# fretscanner-INPUTS.net
KiCad netlist of a schematic drawn in EAGLE
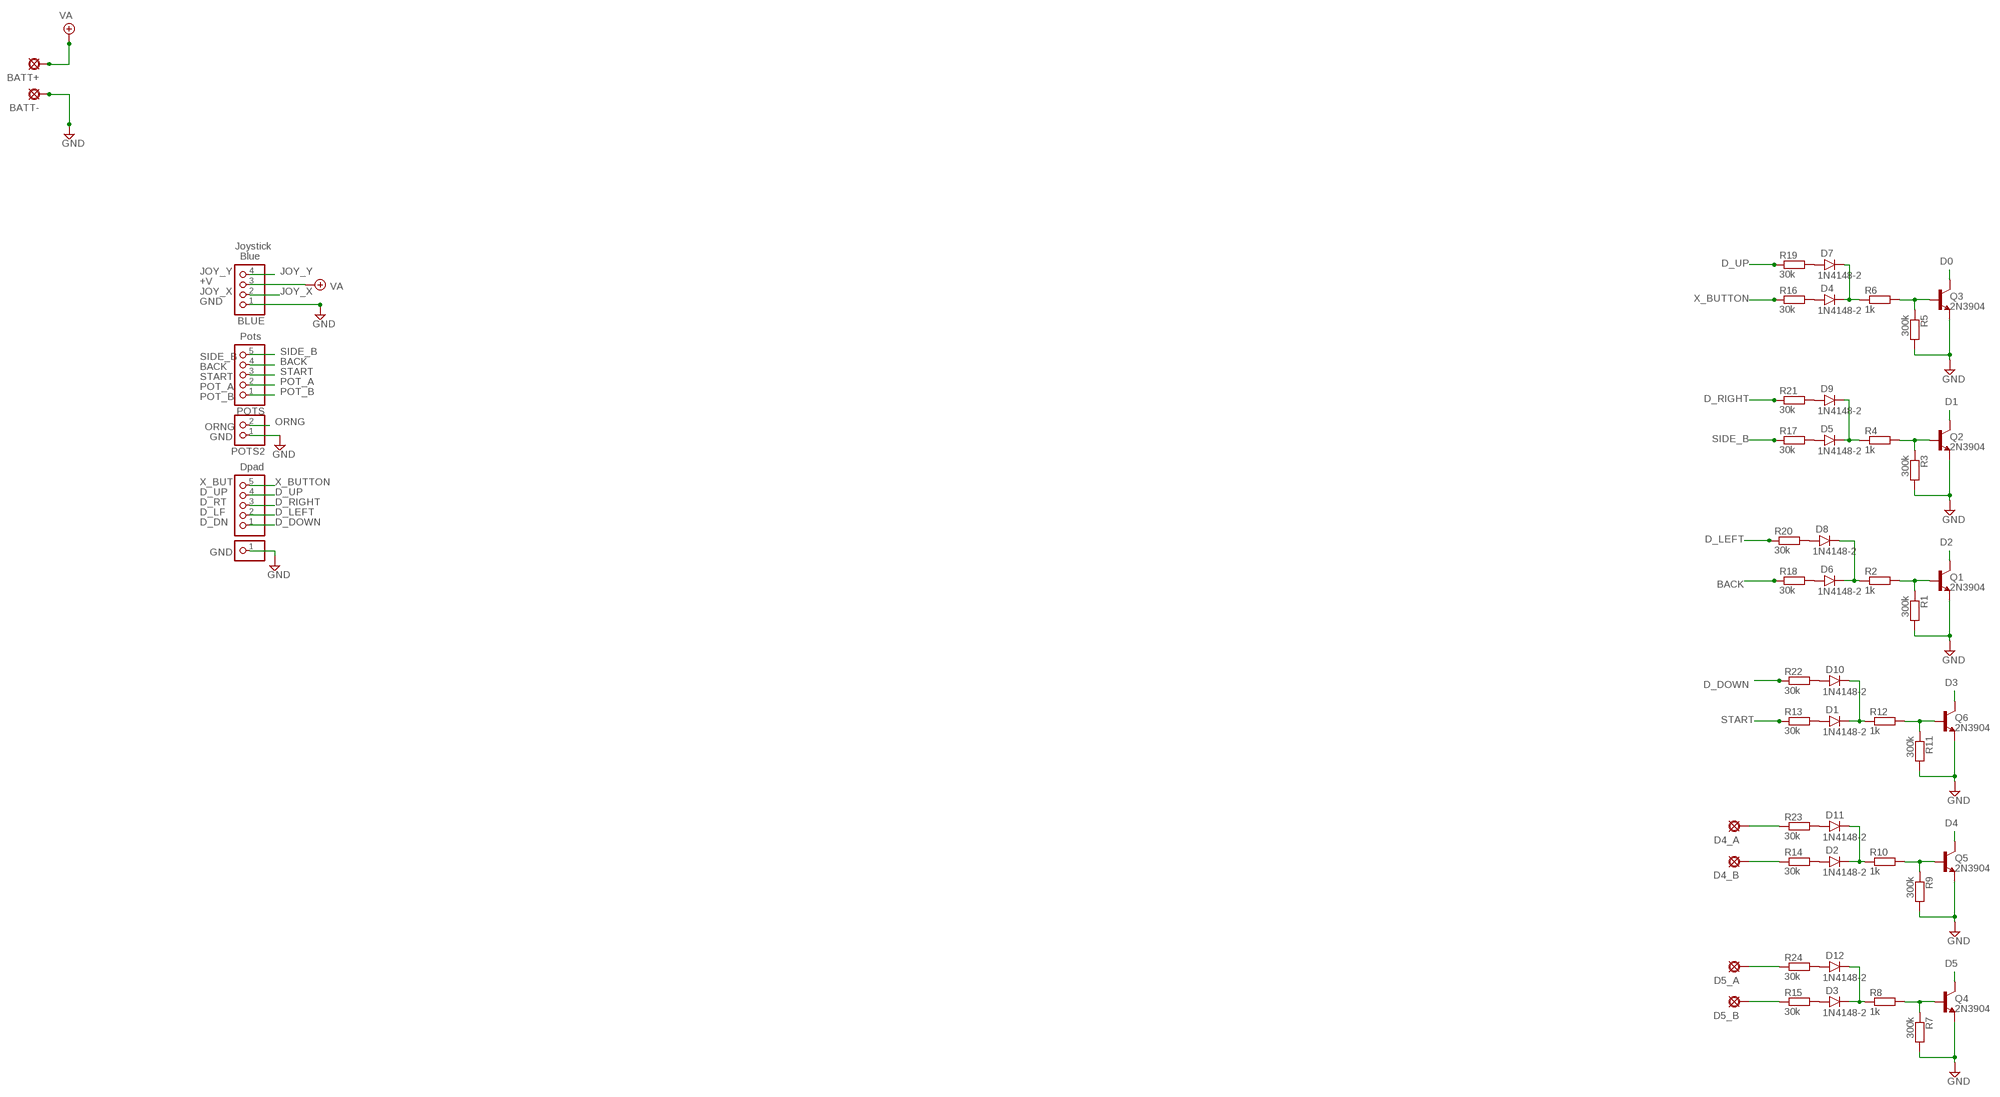
[diagram p0: schematic, sheet 1]

(export (version "E")
  (design (tool "Eeschema 10.0.6"))
  (components
    (comp (ref "BATT+")
      (value "PADL")
      (footprint "eagle-import:LONG")
      (libsource (lib "eagle-import") (part "PADL"))
    )
    (comp (ref "BATT-")
      (value "PADL")
      (footprint "eagle-import:LONG")
      (libsource (lib "eagle-import") (part "PADL"))
    )
    (comp (ref "BLUE")
      (value "PINHD-1X4")
      (footprint "eagle-import:1X04")
      (libsource (lib "eagle-import") (part "PINHD-1X4"))
    )
    (comp (ref "D1")
      (value "1N4148-2")
      (footprint "eagle-import:DO35-2")
      (libsource (lib "eagle-import") (part "1N4148-2"))
    )
    (comp (ref "D2")
      (value "1N4148-2")
      (footprint "eagle-import:DO35-2")
      (libsource (lib "eagle-import") (part "1N4148-2"))
    )
    (comp (ref "D3")
      (value "1N4148-2")
      (footprint "eagle-import:DO35-2")
      (libsource (lib "eagle-import") (part "1N4148-2"))
    )
    (comp (ref "D4")
      (value "1N4148-2")
      (footprint "eagle-import:DO35-2")
      (libsource (lib "eagle-import") (part "1N4148-2"))
    )
    (comp (ref "D4_A")
      (value "PAD")
      (footprint "eagle-import:SQUARE")
      (libsource (lib "eagle-import") (part "PAD"))
    )
    (comp (ref "D4_B")
      (value "PAD")
      (footprint "eagle-import:SQUARE")
      (libsource (lib "eagle-import") (part "PAD"))
    )
    (comp (ref "D5")
      (value "1N4148-2")
      (footprint "eagle-import:DO35-2")
      (libsource (lib "eagle-import") (part "1N4148-2"))
    )
    (comp (ref "D5_A")
      (value "PAD")
      (footprint "eagle-import:SQUARE")
      (libsource (lib "eagle-import") (part "PAD"))
    )
    (comp (ref "D5_B")
      (value "PAD")
      (footprint "eagle-import:SQUARE")
      (libsource (lib "eagle-import") (part "PAD"))
    )
    (comp (ref "D6")
      (value "1N4148-2")
      (footprint "eagle-import:DO35-2")
      (libsource (lib "eagle-import") (part "1N4148-2"))
    )
    (comp (ref "D7")
      (value "1N4148-2")
      (footprint "eagle-import:DO35-2")
      (libsource (lib "eagle-import") (part "1N4148-2"))
    )
    (comp (ref "D8")
      (value "1N4148-2")
      (footprint "eagle-import:DO35-2")
      (libsource (lib "eagle-import") (part "1N4148-2"))
    )
    (comp (ref "D9")
      (value "1N4148-2")
      (footprint "eagle-import:DO35-2")
      (libsource (lib "eagle-import") (part "1N4148-2"))
    )
    (comp (ref "D10")
      (value "1N4148-2")
      (footprint "eagle-import:DO35-2")
      (libsource (lib "eagle-import") (part "1N4148-2"))
    )
    (comp (ref "D11")
      (value "1N4148-2")
      (footprint "eagle-import:DO35-2")
      (libsource (lib "eagle-import") (part "1N4148-2"))
    )
    (comp (ref "D12")
      (value "1N4148-2")
      (footprint "eagle-import:DO35-2")
      (libsource (lib "eagle-import") (part "1N4148-2"))
    )
    (comp (ref "DPAD")
      (value "PINHD-1X5")
      (footprint "eagle-import:1X05")
      (libsource (lib "eagle-import") (part "PINHD-1X5"))
    )
    (comp (ref "DPAD2")
      (value "PINHD-1X1")
      (footprint "eagle-import:1X01")
      (libsource (lib "eagle-import") (part "PINHD-1X1"))
    )
    (comp (ref "POTS")
      (value "PINHD-1X5")
      (footprint "eagle-import:1X05")
      (libsource (lib "eagle-import") (part "PINHD-1X5"))
    )
    (comp (ref "POTS2")
      (value "PINHD-1X2")
      (footprint "eagle-import:1X02")
      (libsource (lib "eagle-import") (part "PINHD-1X2"))
    )
    (comp (ref "Q1")
      (value "2N3904")
      (footprint "eagle-import:TO92-")
      (libsource (lib "eagle-import") (part "2N3904"))
    )
    (comp (ref "Q2")
      (value "2N3904")
      (footprint "eagle-import:TO92-")
      (libsource (lib "eagle-import") (part "2N3904"))
    )
    (comp (ref "Q3")
      (value "2N3904")
      (footprint "eagle-import:TO92-")
      (libsource (lib "eagle-import") (part "2N3904"))
    )
    (comp (ref "Q4")
      (value "2N3904")
      (footprint "eagle-import:TO92-")
      (libsource (lib "eagle-import") (part "2N3904"))
    )
    (comp (ref "Q5")
      (value "2N3904")
      (footprint "eagle-import:TO92-")
      (libsource (lib "eagle-import") (part "2N3904"))
    )
    (comp (ref "Q6")
      (value "2N3904")
      (footprint "eagle-import:TO92-")
      (libsource (lib "eagle-import") (part "2N3904"))
    )
    (comp (ref "R1")
      (value "300k")
      (footprint "eagle-import:R0207_1V")
      (libsource (lib "eagle-import") (part "6MM-EU1"))
    )
    (comp (ref "R2")
      (value "1k")
      (footprint "eagle-import:R0207_1V")
      (libsource (lib "eagle-import") (part "6MM-EU1"))
    )
    (comp (ref "R3")
      (value "300k")
      (footprint "eagle-import:R0207_1V")
      (libsource (lib "eagle-import") (part "6MM-EU1"))
    )
    (comp (ref "R4")
      (value "1k")
      (footprint "eagle-import:R0207_1V")
      (libsource (lib "eagle-import") (part "6MM-EU1"))
    )
    (comp (ref "R5")
      (value "300k")
      (footprint "eagle-import:R0207_1V")
      (libsource (lib "eagle-import") (part "6MM-EU1"))
    )
    (comp (ref "R6")
      (value "1k")
      (footprint "eagle-import:R0207_1V")
      (libsource (lib "eagle-import") (part "6MM-EU1"))
    )
    (comp (ref "R7")
      (value "300k")
      (footprint "eagle-import:R0207_1V")
      (libsource (lib "eagle-import") (part "6MM-EU1"))
    )
    (comp (ref "R8")
      (value "1k")
      (footprint "eagle-import:R0207_1V")
      (libsource (lib "eagle-import") (part "6MM-EU1"))
    )
    (comp (ref "R9")
      (value "300k")
      (footprint "eagle-import:R0207_1V")
      (libsource (lib "eagle-import") (part "6MM-EU1"))
    )
    (comp (ref "R10")
      (value "1k")
      (footprint "eagle-import:R0207_1V")
      (libsource (lib "eagle-import") (part "6MM-EU1"))
    )
    (comp (ref "R11")
      (value "300k")
      (footprint "eagle-import:R0207_1V")
      (libsource (lib "eagle-import") (part "6MM-EU1"))
    )
    (comp (ref "R12")
      (value "1k")
      (footprint "eagle-import:R0207_1V")
      (libsource (lib "eagle-import") (part "6MM-EU1"))
    )
    (comp (ref "R13")
      (value "30k")
      (footprint "eagle-import:R0207_3")
      (libsource (lib "eagle-import") (part "6MM-EU"))
    )
    (comp (ref "R14")
      (value "30k")
      (footprint "eagle-import:R0207_3")
      (libsource (lib "eagle-import") (part "6MM-EU"))
    )
    (comp (ref "R15")
      (value "30k")
      (footprint "eagle-import:R0207_3")
      (libsource (lib "eagle-import") (part "6MM-EU"))
    )
    (comp (ref "R16")
      (value "30k")
      (footprint "eagle-import:R0207_3")
      (libsource (lib "eagle-import") (part "6MM-EU"))
    )
    (comp (ref "R17")
      (value "30k")
      (footprint "eagle-import:R0207_3")
      (libsource (lib "eagle-import") (part "6MM-EU"))
    )
    (comp (ref "R18")
      (value "30k")
      (footprint "eagle-import:R0207_3")
      (libsource (lib "eagle-import") (part "6MM-EU"))
    )
    (comp (ref "R19")
      (value "30k")
      (footprint "eagle-import:R0207_3")
      (libsource (lib "eagle-import") (part "6MM-EU"))
    )
    (comp (ref "R20")
      (value "30k")
      (footprint "eagle-import:R0207_3")
      (libsource (lib "eagle-import") (part "6MM-EU"))
    )
    (comp (ref "R21")
      (value "30k")
      (footprint "eagle-import:R0207_3")
      (libsource (lib "eagle-import") (part "6MM-EU"))
    )
    (comp (ref "R22")
      (value "30k")
      (footprint "eagle-import:R0207_3")
      (libsource (lib "eagle-import") (part "6MM-EU"))
    )
    (comp (ref "R23")
      (value "30k")
      (footprint "eagle-import:R0207_3")
      (libsource (lib "eagle-import") (part "6MM-EU"))
    )
    (comp (ref "R24")
      (value "30k")
      (footprint "eagle-import:R0207_3")
      (libsource (lib "eagle-import") (part "6MM-EU"))
    )
  )
  (nets
    (net (code "1") (name "/BACK") (class "Default")
      (node (ref "POTS") (pin "4") (pinfunction "4_4") (pintype "passive"))
      (node (ref "R18") (pin "1") (pinfunction "1_1") (pintype "passive"))
    )
    (net (code "2") (name "/D0") (class "Default")
      (node (ref "Q3") (pin "1") (pinfunction "C_1") (pintype "passive"))
    )
    (net (code "3") (name "/D1") (class "Default")
      (node (ref "Q2") (pin "1") (pinfunction "C_1") (pintype "passive"))
    )
    (net (code "4") (name "/D2") (class "Default")
      (node (ref "Q1") (pin "1") (pinfunction "C_1") (pintype "passive"))
    )
    (net (code "5") (name "/D3") (class "Default")
      (node (ref "Q6") (pin "1") (pinfunction "C_1") (pintype "passive"))
    )
    (net (code "6") (name "/D4") (class "Default")
      (node (ref "Q5") (pin "1") (pinfunction "C_1") (pintype "passive"))
    )
    (net (code "7") (name "/D5") (class "Default")
      (node (ref "Q4") (pin "1") (pinfunction "C_1") (pintype "passive"))
    )
    (net (code "8") (name "/D_DOWN") (class "Default")
      (node (ref "DPAD") (pin "1") (pinfunction "1_1") (pintype "passive"))
      (node (ref "R22") (pin "1") (pinfunction "1_1") (pintype "passive"))
    )
    (net (code "9") (name "/D_LEFT") (class "Default")
      (node (ref "DPAD") (pin "2") (pinfunction "2_2") (pintype "passive"))
      (node (ref "R20") (pin "1") (pinfunction "1_1") (pintype "passive"))
    )
    (net (code "10") (name "/D_RIGHT") (class "Default")
      (node (ref "DPAD") (pin "3") (pinfunction "3_3") (pintype "passive"))
      (node (ref "R21") (pin "1") (pinfunction "1_1") (pintype "passive"))
    )
    (net (code "11") (name "/D_UP") (class "Default")
      (node (ref "DPAD") (pin "4") (pinfunction "4_4") (pintype "passive"))
      (node (ref "R19") (pin "1") (pinfunction "1_1") (pintype "passive"))
    )
    (net (code "12") (name "/JOY_X") (class "Default")
      (node (ref "BLUE") (pin "2") (pinfunction "2_2") (pintype "passive"))
    )
    (net (code "13") (name "/JOY_Y") (class "Default")
      (node (ref "BLUE") (pin "4") (pinfunction "4_4") (pintype "passive"))
    )
    (net (code "14") (name "/ORNG") (class "Default")
      (node (ref "POTS2") (pin "2") (pinfunction "2_2") (pintype "passive"))
    )
    (net (code "15") (name "/POT_A") (class "Default")
      (node (ref "POTS") (pin "2") (pinfunction "2_2") (pintype "passive"))
    )
    (net (code "16") (name "/POT_B") (class "Default")
      (node (ref "POTS") (pin "1") (pinfunction "1_1") (pintype "passive"))
    )
    (net (code "17") (name "/SIDE_B") (class "Default")
      (node (ref "POTS") (pin "5") (pinfunction "5_5") (pintype "passive"))
      (node (ref "R17") (pin "1") (pinfunction "1_1") (pintype "passive"))
    )
    (net (code "18") (name "/START") (class "Default")
      (node (ref "POTS") (pin "3") (pinfunction "3_3") (pintype "passive"))
      (node (ref "R13") (pin "1") (pinfunction "1_1") (pintype "passive"))
    )
    (net (code "19") (name "/X_BUTTON") (class "Default")
      (node (ref "DPAD") (pin "5") (pinfunction "5_5") (pintype "passive"))
      (node (ref "R16") (pin "1") (pinfunction "1_1") (pintype "passive"))
    )
    (net (code "20") (name "GND") (class "Default")
      (node (ref "BATT-") (pin "1") (pinfunction "PAD_1") (pintype "passive"))
      (node (ref "BLUE") (pin "1") (pinfunction "1_1") (pintype "passive"))
      (node (ref "DPAD2") (pin "1") (pinfunction "1_1") (pintype "passive"))
      (node (ref "POTS2") (pin "1") (pinfunction "1_1") (pintype "passive"))
      (node (ref "Q1") (pin "3") (pinfunction "E_3") (pintype "passive"))
      (node (ref "Q2") (pin "3") (pinfunction "E_3") (pintype "passive"))
      (node (ref "Q3") (pin "3") (pinfunction "E_3") (pintype "passive"))
      (node (ref "Q4") (pin "3") (pinfunction "E_3") (pintype "passive"))
      (node (ref "Q5") (pin "3") (pinfunction "E_3") (pintype "passive"))
      (node (ref "Q6") (pin "3") (pinfunction "E_3") (pintype "passive"))
      (node (ref "R1") (pin "2") (pinfunction "2_2") (pintype "passive"))
      (node (ref "R11") (pin "2") (pinfunction "2_2") (pintype "passive"))
      (node (ref "R3") (pin "2") (pinfunction "2_2") (pintype "passive"))
      (node (ref "R5") (pin "2") (pinfunction "2_2") (pintype "passive"))
      (node (ref "R7") (pin "2") (pinfunction "2_2") (pintype "passive"))
      (node (ref "R9") (pin "2") (pinfunction "2_2") (pintype "passive"))
    )
    (net (code "21") (name "Net-(D1-PadA)") (class "Default")
      (node (ref "D1") (pin "A") (pinfunction "A_A") (pintype "passive"))
      (node (ref "R13") (pin "2") (pinfunction "2_2") (pintype "passive"))
    )
    (net (code "22") (name "Net-(D1-PadC)") (class "Default")
      (node (ref "D1") (pin "C") (pinfunction "C_C") (pintype "passive"))
      (node (ref "D10") (pin "C") (pinfunction "C_C") (pintype "passive"))
      (node (ref "R12") (pin "1") (pinfunction "1_1") (pintype "passive"))
    )
    (net (code "23") (name "Net-(D2-PadA)") (class "Default")
      (node (ref "D2") (pin "A") (pinfunction "A_A") (pintype "passive"))
      (node (ref "R14") (pin "2") (pinfunction "2_2") (pintype "passive"))
    )
    (net (code "24") (name "Net-(D3-PadA)") (class "Default")
      (node (ref "D3") (pin "A") (pinfunction "A_A") (pintype "passive"))
      (node (ref "R15") (pin "2") (pinfunction "2_2") (pintype "passive"))
    )
    (net (code "25") (name "Net-(D4-PadA)") (class "Default")
      (node (ref "D4") (pin "A") (pinfunction "A_A") (pintype "passive"))
      (node (ref "R16") (pin "2") (pinfunction "2_2") (pintype "passive"))
    )
    (net (code "26") (name "Net-(D4-PadC)") (class "Default")
      (node (ref "D4") (pin "C") (pinfunction "C_C") (pintype "passive"))
      (node (ref "D7") (pin "C") (pinfunction "C_C") (pintype "passive"))
      (node (ref "R6") (pin "1") (pinfunction "1_1") (pintype "passive"))
    )
    (net (code "27") (name "Net-(D4_A-PAD)") (class "Default")
      (node (ref "D4_A") (pin "1") (pinfunction "PAD_1") (pintype "passive"))
      (node (ref "R23") (pin "1") (pinfunction "1_1") (pintype "passive"))
    )
    (net (code "28") (name "Net-(D4_B-PAD)") (class "Default")
      (node (ref "D4_B") (pin "1") (pinfunction "PAD_1") (pintype "passive"))
      (node (ref "R14") (pin "1") (pinfunction "1_1") (pintype "passive"))
    )
    (net (code "29") (name "Net-(D5-PadA)") (class "Default")
      (node (ref "D5") (pin "A") (pinfunction "A_A") (pintype "passive"))
      (node (ref "R17") (pin "2") (pinfunction "2_2") (pintype "passive"))
    )
    (net (code "30") (name "Net-(D5-PadC)") (class "Default")
      (node (ref "D5") (pin "C") (pinfunction "C_C") (pintype "passive"))
      (node (ref "D9") (pin "C") (pinfunction "C_C") (pintype "passive"))
      (node (ref "R4") (pin "1") (pinfunction "1_1") (pintype "passive"))
    )
    (net (code "31") (name "Net-(D5_A-PAD)") (class "Default")
      (node (ref "D5_A") (pin "1") (pinfunction "PAD_1") (pintype "passive"))
      (node (ref "R24") (pin "1") (pinfunction "1_1") (pintype "passive"))
    )
    (net (code "32") (name "Net-(D5_B-PAD)") (class "Default")
      (node (ref "D5_B") (pin "1") (pinfunction "PAD_1") (pintype "passive"))
      (node (ref "R15") (pin "1") (pinfunction "1_1") (pintype "passive"))
    )
    (net (code "33") (name "Net-(D6-PadA)") (class "Default")
      (node (ref "D6") (pin "A") (pinfunction "A_A") (pintype "passive"))
      (node (ref "R18") (pin "2") (pinfunction "2_2") (pintype "passive"))
    )
    (net (code "34") (name "Net-(D6-PadC)") (class "Default")
      (node (ref "D6") (pin "C") (pinfunction "C_C") (pintype "passive"))
      (node (ref "D8") (pin "C") (pinfunction "C_C") (pintype "passive"))
      (node (ref "R2") (pin "1") (pinfunction "1_1") (pintype "passive"))
    )
    (net (code "35") (name "Net-(D7-PadA)") (class "Default")
      (node (ref "D7") (pin "A") (pinfunction "A_A") (pintype "passive"))
      (node (ref "R19") (pin "2") (pinfunction "2_2") (pintype "passive"))
    )
    (net (code "36") (name "Net-(D8-PadA)") (class "Default")
      (node (ref "D8") (pin "A") (pinfunction "A_A") (pintype "passive"))
      (node (ref "R20") (pin "2") (pinfunction "2_2") (pintype "passive"))
    )
    (net (code "37") (name "Net-(D9-PadA)") (class "Default")
      (node (ref "D9") (pin "A") (pinfunction "A_A") (pintype "passive"))
      (node (ref "R21") (pin "2") (pinfunction "2_2") (pintype "passive"))
    )
    (net (code "38") (name "Net-(D10-PadA)") (class "Default")
      (node (ref "D10") (pin "A") (pinfunction "A_A") (pintype "passive"))
      (node (ref "R22") (pin "2") (pinfunction "2_2") (pintype "passive"))
    )
    (net (code "39") (name "Net-(D11-PadA)") (class "Default")
      (node (ref "D11") (pin "A") (pinfunction "A_A") (pintype "passive"))
      (node (ref "R23") (pin "2") (pinfunction "2_2") (pintype "passive"))
    )
    (net (code "40") (name "Net-(D11-PadC)") (class "Default")
      (node (ref "D11") (pin "C") (pinfunction "C_C") (pintype "passive"))
      (node (ref "D2") (pin "C") (pinfunction "C_C") (pintype "passive"))
      (node (ref "R10") (pin "1") (pinfunction "1_1") (pintype "passive"))
    )
    (net (code "41") (name "Net-(D12-PadA)") (class "Default")
      (node (ref "D12") (pin "A") (pinfunction "A_A") (pintype "passive"))
      (node (ref "R24") (pin "2") (pinfunction "2_2") (pintype "passive"))
    )
    (net (code "42") (name "Net-(D12-PadC)") (class "Default")
      (node (ref "D12") (pin "C") (pinfunction "C_C") (pintype "passive"))
      (node (ref "D3") (pin "C") (pinfunction "C_C") (pintype "passive"))
      (node (ref "R8") (pin "1") (pinfunction "1_1") (pintype "passive"))
    )
    (net (code "43") (name "Net-(Q1-B)") (class "Default")
      (node (ref "Q1") (pin "2") (pinfunction "B_2") (pintype "passive"))
      (node (ref "R1") (pin "1") (pinfunction "1_1") (pintype "passive"))
      (node (ref "R2") (pin "2") (pinfunction "2_2") (pintype "passive"))
    )
    (net (code "44") (name "Net-(Q2-B)") (class "Default")
      (node (ref "Q2") (pin "2") (pinfunction "B_2") (pintype "passive"))
      (node (ref "R3") (pin "1") (pinfunction "1_1") (pintype "passive"))
      (node (ref "R4") (pin "2") (pinfunction "2_2") (pintype "passive"))
    )
    (net (code "45") (name "Net-(Q3-B)") (class "Default")
      (node (ref "Q3") (pin "2") (pinfunction "B_2") (pintype "passive"))
      (node (ref "R5") (pin "1") (pinfunction "1_1") (pintype "passive"))
      (node (ref "R6") (pin "2") (pinfunction "2_2") (pintype "passive"))
    )
    (net (code "46") (name "Net-(Q4-B)") (class "Default")
      (node (ref "Q4") (pin "2") (pinfunction "B_2") (pintype "passive"))
      (node (ref "R7") (pin "1") (pinfunction "1_1") (pintype "passive"))
      (node (ref "R8") (pin "2") (pinfunction "2_2") (pintype "passive"))
    )
    (net (code "47") (name "Net-(Q5-B)") (class "Default")
      (node (ref "Q5") (pin "2") (pinfunction "B_2") (pintype "passive"))
      (node (ref "R10") (pin "2") (pinfunction "2_2") (pintype "passive"))
      (node (ref "R9") (pin "1") (pinfunction "1_1") (pintype "passive"))
    )
    (net (code "48") (name "Net-(Q6-B)") (class "Default")
      (node (ref "Q6") (pin "2") (pinfunction "B_2") (pintype "passive"))
      (node (ref "R11") (pin "1") (pinfunction "1_1") (pintype "passive"))
      (node (ref "R12") (pin "2") (pinfunction "2_2") (pintype "passive"))
    )
    (net (code "49") (name "VA") (class "Default")
      (node (ref "BATT+") (pin "1") (pinfunction "PAD_1") (pintype "passive"))
      (node (ref "BLUE") (pin "3") (pinfunction "3_3") (pintype "passive"))
    )
  )
)
